# 16CH_PWM_POWER_00.net
KiCad netlist of a schematic drawn in Altium Designer
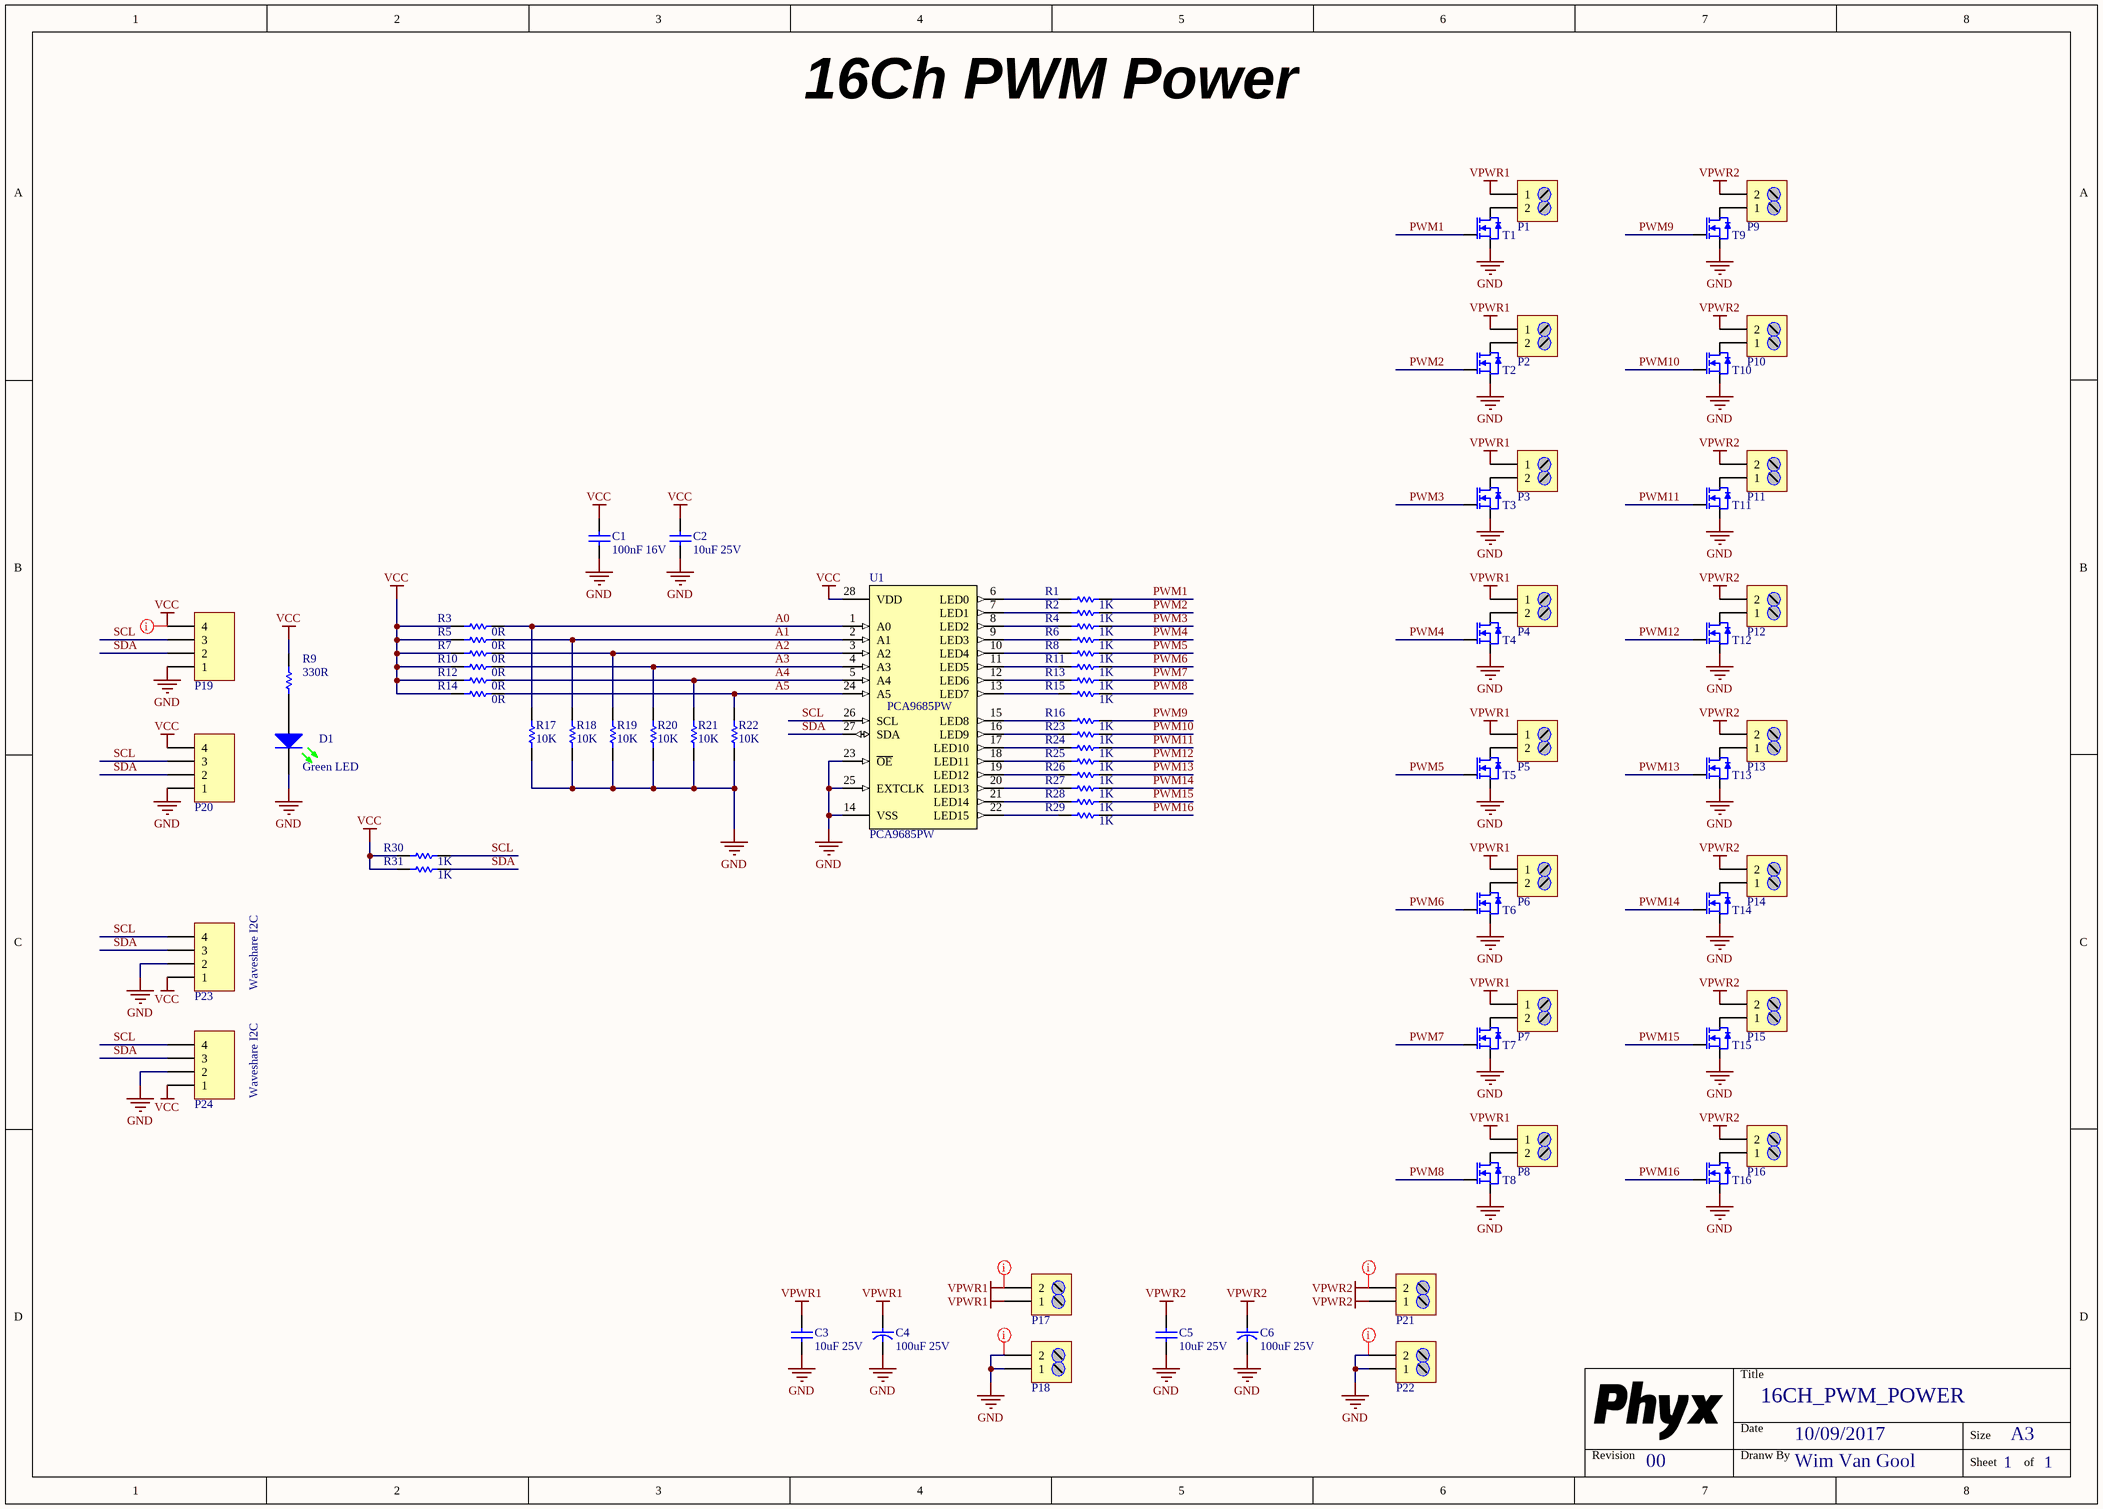
[diagram p0: 16CH_PWM_POWER_00.SchDoc]

(export (version "E")
  (design (tool "Eeschema 10.0.6"))
  (components
    (comp (ref "C1")
      (value "100nF 16V")
      (footprint "C0603_N")
      (description "Capacitor Ceramic")
      (fields (field (name "Comment") "CAP_CERAMIC"))
      (libsource (lib "Phyx_Components") (part "CAP_CERAMIC"))
    )
    (comp (ref "C2")
      (value "10uF 25V")
      (footprint "C1206_N")
      (description "Capacitor Ceramic")
      (fields (field (name "Comment") "CAP_CERAMIC"))
      (libsource (lib "Phyx_Components") (part "CAP_CERAMIC"))
    )
    (comp (ref "C3")
      (value "10uF 25V")
      (footprint "C1206_N")
      (description "Capacitor Ceramic")
      (fields (field (name "Comment") "CAP_CERAMIC"))
      (libsource (lib "Phyx_Components") (part "CAP_CERAMIC"))
    )
    (comp (ref "C4")
      (value "100uF 25V")
      (footprint "C_8x11.5_3.5mm")
      (description "Capacitor electrolyt")
      (fields (field (name "Comment") "CAP_POL"))
      (libsource (lib "Phyx_Components") (part "CAP_POL"))
    )
    (comp (ref "C5")
      (value "10uF 25V")
      (footprint "C1206_N")
      (description "Capacitor Ceramic")
      (fields (field (name "Comment") "CAP_CERAMIC"))
      (libsource (lib "Phyx_Components") (part "CAP_CERAMIC"))
    )
    (comp (ref "C6")
      (value "100uF 25V")
      (footprint "C_8x11.5_3.5mm")
      (description "Capacitor electrolyt")
      (fields (field (name "Comment") "CAP_POL"))
      (libsource (lib "Phyx_Components") (part "CAP_POL"))
    )
    (comp (ref "D1")
      (value "Green LED")
      (footprint "LED_0805_GR")
      (description "=Description")
      (libsource (lib "Phyx_Components") (part "LED_GREEN"))
    )
    (comp (ref "P1")
      (value "2 Way Screw HDR 3,5mm")
      (footprint "WE_691103110002")
      (libsource (lib "Phyx_Components") (part "TERM_BLCK_2"))
    )
    (comp (ref "P2")
      (value "2 Way Screw HDR 3,5mm")
      (footprint "WE_691103110002")
      (libsource (lib "Phyx_Components") (part "TERM_BLCK_2"))
    )
    (comp (ref "P3")
      (value "2 Way Screw HDR 3,5mm")
      (footprint "WE_691103110002")
      (libsource (lib "Phyx_Components") (part "TERM_BLCK_2"))
    )
    (comp (ref "P4")
      (value "2 Way Screw HDR 3,5mm")
      (footprint "WE_691103110002")
      (libsource (lib "Phyx_Components") (part "TERM_BLCK_2"))
    )
    (comp (ref "P5")
      (value "2 Way Screw HDR 3,5mm")
      (footprint "WE_691103110002")
      (libsource (lib "Phyx_Components") (part "TERM_BLCK_2"))
    )
    (comp (ref "P6")
      (value "2 Way Screw HDR 3,5mm")
      (footprint "WE_691103110002")
      (libsource (lib "Phyx_Components") (part "TERM_BLCK_2"))
    )
    (comp (ref "P7")
      (value "2 Way Screw HDR 3,5mm")
      (footprint "WE_691103110002")
      (libsource (lib "Phyx_Components") (part "TERM_BLCK_2"))
    )
    (comp (ref "P8")
      (value "2 Way Screw HDR 3,5mm")
      (footprint "WE_691103110002")
      (libsource (lib "Phyx_Components") (part "TERM_BLCK_2"))
    )
    (comp (ref "P9")
      (value "2 Way Screw HDR 3,5mm")
      (footprint "WE_691103110002")
      (libsource (lib "") (part "TERM_BLCK_2_1"))
    )
    (comp (ref "P10")
      (value "2 Way Screw HDR 3,5mm")
      (footprint "WE_691103110002")
      (libsource (lib "") (part "TERM_BLCK_2_1"))
    )
    (comp (ref "P11")
      (value "2 Way Screw HDR 3,5mm")
      (footprint "WE_691103110002")
      (libsource (lib "") (part "TERM_BLCK_2_1"))
    )
    (comp (ref "P12")
      (value "2 Way Screw HDR 3,5mm")
      (footprint "WE_691103110002")
      (libsource (lib "") (part "TERM_BLCK_2_1"))
    )
    (comp (ref "P13")
      (value "2 Way Screw HDR 3,5mm")
      (footprint "WE_691103110002")
      (libsource (lib "") (part "TERM_BLCK_2_1"))
    )
    (comp (ref "P14")
      (value "2 Way Screw HDR 3,5mm")
      (footprint "WE_691103110002")
      (libsource (lib "") (part "TERM_BLCK_2_1"))
    )
    (comp (ref "P15")
      (value "2 Way Screw HDR 3,5mm")
      (footprint "WE_691103110002")
      (libsource (lib "") (part "TERM_BLCK_2_1"))
    )
    (comp (ref "P16")
      (value "2 Way Screw HDR 3,5mm")
      (footprint "WE_691103110002")
      (libsource (lib "") (part "TERM_BLCK_2_1"))
    )
    (comp (ref "P17")
      (value "2 Way Screw HDR 3,5mm")
      (footprint "WE_691103110002")
      (libsource (lib "") (part "TERM_BLCK_2_1"))
    )
    (comp (ref "P18")
      (value "2 Way Screw HDR 3,5mm")
      (footprint "WE_691103110002")
      (libsource (lib "") (part "TERM_BLCK_2_1"))
    )
    (comp (ref "P19")
      (value "Header 4")
      (footprint "HDR1X4")
      (libsource (lib "Phyx_Components") (part "Header 4"))
    )
    (comp (ref "P20")
      (value "Header 4")
      (footprint "HDR1X4")
      (libsource (lib "Phyx_Components") (part "Header 4"))
    )
    (comp (ref "P21")
      (value "2 Way Screw HDR 3,5mm")
      (footprint "WE_691103110002")
      (libsource (lib "") (part "TERM_BLCK_2_1"))
    )
    (comp (ref "P22")
      (value "2 Way Screw HDR 3,5mm")
      (footprint "WE_691103110002")
      (libsource (lib "") (part "TERM_BLCK_2_1"))
    )
    (comp (ref "P23")
      (value "Header 4")
      (footprint "HDR1X4")
      (libsource (lib "Phyx_Components") (part "Header 4"))
    )
    (comp (ref "P24")
      (value "Header 4")
      (footprint "HDR1X4")
      (libsource (lib "Phyx_Components") (part "Header 4"))
    )
    (comp (ref "R1")
      (value "1K")
      (footprint "R0603_N")
      (fields (field (name "Comment") "RESISTOR"))
      (libsource (lib "Phyx_Components") (part "RESISTOR"))
    )
    (comp (ref "R2")
      (value "1K")
      (footprint "R0603_N")
      (fields (field (name "Comment") "RESISTOR"))
      (libsource (lib "Phyx_Components") (part "RESISTOR"))
    )
    (comp (ref "R3")
      (value "0R")
      (footprint "R0603_N")
      (fields (field (name "Comment") "RESISTOR"))
      (libsource (lib "Phyx_Components") (part "RESISTOR"))
    )
    (comp (ref "R4")
      (value "1K")
      (footprint "R0603_N")
      (fields (field (name "Comment") "RESISTOR"))
      (libsource (lib "Phyx_Components") (part "RESISTOR"))
    )
    (comp (ref "R5")
      (value "0R")
      (footprint "R0603_N")
      (fields (field (name "Comment") "RESISTOR"))
      (libsource (lib "Phyx_Components") (part "RESISTOR"))
    )
    (comp (ref "R6")
      (value "1K")
      (footprint "R0603_N")
      (fields (field (name "Comment") "RESISTOR"))
      (libsource (lib "Phyx_Components") (part "RESISTOR"))
    )
    (comp (ref "R7")
      (value "0R")
      (footprint "R0603_N")
      (fields (field (name "Comment") "RESISTOR"))
      (libsource (lib "Phyx_Components") (part "RESISTOR"))
    )
    (comp (ref "R8")
      (value "1K")
      (footprint "R0603_N")
      (fields (field (name "Comment") "RESISTOR"))
      (libsource (lib "Phyx_Components") (part "RESISTOR"))
    )
    (comp (ref "R9")
      (value "330R")
      (footprint "R0603_N")
      (fields (field (name "Comment") "RESISTOR"))
      (libsource (lib "Phyx_Components") (part "RESISTOR"))
    )
    (comp (ref "R10")
      (value "0R")
      (footprint "R0603_N")
      (fields (field (name "Comment") "RESISTOR"))
      (libsource (lib "Phyx_Components") (part "RESISTOR"))
    )
    (comp (ref "R11")
      (value "1K")
      (footprint "R0603_N")
      (fields (field (name "Comment") "RESISTOR"))
      (libsource (lib "Phyx_Components") (part "RESISTOR"))
    )
    (comp (ref "R12")
      (value "0R")
      (footprint "R0603_N")
      (fields (field (name "Comment") "RESISTOR"))
      (libsource (lib "Phyx_Components") (part "RESISTOR"))
    )
    (comp (ref "R13")
      (value "1K")
      (footprint "R0603_N")
      (fields (field (name "Comment") "RESISTOR"))
      (libsource (lib "Phyx_Components") (part "RESISTOR"))
    )
    (comp (ref "R14")
      (value "0R")
      (footprint "R0603_N")
      (fields (field (name "Comment") "RESISTOR"))
      (libsource (lib "Phyx_Components") (part "RESISTOR"))
    )
    (comp (ref "R15")
      (value "1K")
      (footprint "R0603_N")
      (fields (field (name "Comment") "RESISTOR"))
      (libsource (lib "Phyx_Components") (part "RESISTOR"))
    )
    (comp (ref "R16")
      (value "1K")
      (footprint "R0603_N")
      (fields (field (name "Comment") "RESISTOR"))
      (libsource (lib "Phyx_Components") (part "RESISTOR"))
    )
    (comp (ref "R17")
      (value "10K")
      (footprint "R0603_N")
      (fields (field (name "Comment") "RESISTOR"))
      (libsource (lib "Phyx_Components") (part "RESISTOR"))
    )
    (comp (ref "R18")
      (value "10K")
      (footprint "R0603_N")
      (fields (field (name "Comment") "RESISTOR"))
      (libsource (lib "Phyx_Components") (part "RESISTOR"))
    )
    (comp (ref "R19")
      (value "10K")
      (footprint "R0603_N")
      (fields (field (name "Comment") "RESISTOR"))
      (libsource (lib "Phyx_Components") (part "RESISTOR"))
    )
    (comp (ref "R20")
      (value "10K")
      (footprint "R0603_N")
      (fields (field (name "Comment") "RESISTOR"))
      (libsource (lib "Phyx_Components") (part "RESISTOR"))
    )
    (comp (ref "R21")
      (value "10K")
      (footprint "R0603_N")
      (fields (field (name "Comment") "RESISTOR"))
      (libsource (lib "Phyx_Components") (part "RESISTOR"))
    )
    (comp (ref "R22")
      (value "10K")
      (footprint "R0603_N")
      (fields (field (name "Comment") "RESISTOR"))
      (libsource (lib "Phyx_Components") (part "RESISTOR"))
    )
    (comp (ref "R23")
      (value "1K")
      (footprint "R0603_N")
      (fields (field (name "Comment") "RESISTOR"))
      (libsource (lib "Phyx_Components") (part "RESISTOR"))
    )
    (comp (ref "R24")
      (value "1K")
      (footprint "R0603_N")
      (fields (field (name "Comment") "RESISTOR"))
      (libsource (lib "Phyx_Components") (part "RESISTOR"))
    )
    (comp (ref "R25")
      (value "1K")
      (footprint "R0603_N")
      (fields (field (name "Comment") "RESISTOR"))
      (libsource (lib "Phyx_Components") (part "RESISTOR"))
    )
    (comp (ref "R26")
      (value "1K")
      (footprint "R0603_N")
      (fields (field (name "Comment") "RESISTOR"))
      (libsource (lib "Phyx_Components") (part "RESISTOR"))
    )
    (comp (ref "R27")
      (value "1K")
      (footprint "R0603_N")
      (fields (field (name "Comment") "RESISTOR"))
      (libsource (lib "Phyx_Components") (part "RESISTOR"))
    )
    (comp (ref "R28")
      (value "1K")
      (footprint "R0603_N")
      (fields (field (name "Comment") "RESISTOR"))
      (libsource (lib "Phyx_Components") (part "RESISTOR"))
    )
    (comp (ref "R29")
      (value "1K")
      (footprint "R0603_N")
      (fields (field (name "Comment") "RESISTOR"))
      (libsource (lib "Phyx_Components") (part "RESISTOR"))
    )
    (comp (ref "R30")
      (value "1K")
      (footprint "R0603_N")
      (fields (field (name "Comment") "RESISTOR"))
      (libsource (lib "Phyx_Components") (part "RESISTOR"))
    )
    (comp (ref "R31")
      (value "1K")
      (footprint "R0603_N")
      (fields (field (name "Comment") "RESISTOR"))
      (libsource (lib "Phyx_Components") (part "RESISTOR"))
    )
    (comp (ref "T1")
      (value "70A 30V N-Ch MOSFET Vgs 2.5")
      (footprint "TO-252")
      (libsource (lib "Phyx_Components") (part "N_MOSFET_GSD"))
    )
    (comp (ref "T2")
      (value "70A 30V N-Ch MOSFET Vgs 2.5")
      (footprint "TO-252")
      (libsource (lib "Phyx_Components") (part "N_MOSFET_GSD"))
    )
    (comp (ref "T3")
      (value "70A 30V N-Ch MOSFET Vgs 2.5")
      (footprint "TO-252")
      (libsource (lib "Phyx_Components") (part "N_MOSFET_GSD"))
    )
    (comp (ref "T4")
      (value "70A 30V N-Ch MOSFET Vgs 2.5")
      (footprint "TO-252")
      (libsource (lib "Phyx_Components") (part "N_MOSFET_GSD"))
    )
    (comp (ref "T5")
      (value "70A 30V N-Ch MOSFET Vgs 2.5")
      (footprint "TO-252")
      (libsource (lib "Phyx_Components") (part "N_MOSFET_GSD"))
    )
    (comp (ref "T6")
      (value "70A 30V N-Ch MOSFET Vgs 2.5")
      (footprint "TO-252")
      (libsource (lib "Phyx_Components") (part "N_MOSFET_GSD"))
    )
    (comp (ref "T7")
      (value "70A 30V N-Ch MOSFET Vgs 2.5")
      (footprint "TO-252")
      (libsource (lib "Phyx_Components") (part "N_MOSFET_GSD"))
    )
    (comp (ref "T8")
      (value "70A 30V N-Ch MOSFET Vgs 2.5")
      (footprint "TO-252")
      (libsource (lib "Phyx_Components") (part "N_MOSFET_GSD"))
    )
    (comp (ref "T9")
      (value "70A 30V N-Ch MOSFET Vgs 2.5")
      (footprint "TO-252")
      (libsource (lib "Phyx_Components") (part "N_MOSFET_GSD"))
    )
    (comp (ref "T10")
      (value "70A 30V N-Ch MOSFET Vgs 2.5")
      (footprint "TO-252")
      (libsource (lib "Phyx_Components") (part "N_MOSFET_GSD"))
    )
    (comp (ref "T11")
      (value "70A 30V N-Ch MOSFET Vgs 2.5")
      (footprint "TO-252")
      (libsource (lib "Phyx_Components") (part "N_MOSFET_GSD"))
    )
    (comp (ref "T12")
      (value "70A 30V N-Ch MOSFET Vgs 2.5")
      (footprint "TO-252")
      (libsource (lib "Phyx_Components") (part "N_MOSFET_GSD"))
    )
    (comp (ref "T13")
      (value "70A 30V N-Ch MOSFET Vgs 2.5")
      (footprint "TO-252")
      (libsource (lib "Phyx_Components") (part "N_MOSFET_GSD"))
    )
    (comp (ref "T14")
      (value "70A 30V N-Ch MOSFET Vgs 2.5")
      (footprint "TO-252")
      (libsource (lib "Phyx_Components") (part "N_MOSFET_GSD"))
    )
    (comp (ref "T15")
      (value "70A 30V N-Ch MOSFET Vgs 2.5")
      (footprint "TO-252")
      (libsource (lib "Phyx_Components") (part "N_MOSFET_GSD"))
    )
    (comp (ref "T16")
      (value "70A 30V N-Ch MOSFET Vgs 2.5")
      (footprint "TO-252")
      (libsource (lib "Phyx_Components") (part "N_MOSFET_GSD"))
    )
    (comp (ref "U1")
      (value "PCA9685PW")
      (footprint "NXP_SOT361-1")
      (description "=Description")
      (fields (field (name "Comment") "I2C 12-bit 16Ch PWM"))
      (libsource (lib "Phyx_Components") (part "PCA9685PW"))
    )
  )
  (nets
    (net (code "1") (name "/A0") (class "Default")
      (node (ref "R17") (pin "1") (pinfunction "1_1") (pintype "passive"))
      (node (ref "R3") (pin "2") (pinfunction "2_2") (pintype "passive"))
      (node (ref "U1") (pin "1") (pinfunction "A0_1") (pintype "input"))
    )
    (net (code "2") (name "/A1") (class "Default")
      (node (ref "R18") (pin "1") (pinfunction "1_1") (pintype "passive"))
      (node (ref "R5") (pin "2") (pinfunction "2_2") (pintype "passive"))
      (node (ref "U1") (pin "2") (pinfunction "A1_2") (pintype "input"))
    )
    (net (code "3") (name "/A2") (class "Default")
      (node (ref "R19") (pin "1") (pinfunction "1_1") (pintype "passive"))
      (node (ref "R7") (pin "2") (pinfunction "2_2") (pintype "passive"))
      (node (ref "U1") (pin "3") (pinfunction "A2_3") (pintype "input"))
    )
    (net (code "4") (name "/A3") (class "Default")
      (node (ref "R10") (pin "2") (pinfunction "2_2") (pintype "passive"))
      (node (ref "R20") (pin "1") (pinfunction "1_1") (pintype "passive"))
      (node (ref "U1") (pin "4") (pinfunction "A3_4") (pintype "input"))
    )
    (net (code "5") (name "/A4") (class "Default")
      (node (ref "R12") (pin "2") (pinfunction "2_2") (pintype "passive"))
      (node (ref "R21") (pin "1") (pinfunction "1_1") (pintype "passive"))
      (node (ref "U1") (pin "5") (pinfunction "A4_5") (pintype "input"))
    )
    (net (code "6") (name "/A5") (class "Default")
      (node (ref "R14") (pin "2") (pinfunction "2_2") (pintype "passive"))
      (node (ref "R22") (pin "1") (pinfunction "1_1") (pintype "passive"))
      (node (ref "U1") (pin "24") (pinfunction "A5_24") (pintype "input"))
    )
    (net (code "7") (name "/PWM1") (class "Default")
      (node (ref "R1") (pin "1") (pinfunction "1_1") (pintype "passive"))
      (node (ref "T1") (pin "1") (pinfunction "G_1") (pintype "passive"))
    )
    (net (code "8") (name "/PWM2") (class "Default")
      (node (ref "R2") (pin "1") (pinfunction "1_1") (pintype "passive"))
      (node (ref "T2") (pin "1") (pinfunction "G_1") (pintype "passive"))
    )
    (net (code "9") (name "/PWM3") (class "Default")
      (node (ref "R4") (pin "1") (pinfunction "1_1") (pintype "passive"))
      (node (ref "T3") (pin "1") (pinfunction "G_1") (pintype "passive"))
    )
    (net (code "10") (name "/PWM4") (class "Default")
      (node (ref "R6") (pin "1") (pinfunction "1_1") (pintype "passive"))
      (node (ref "T4") (pin "1") (pinfunction "G_1") (pintype "passive"))
    )
    (net (code "11") (name "/PWM5") (class "Default")
      (node (ref "R8") (pin "1") (pinfunction "1_1") (pintype "passive"))
      (node (ref "T5") (pin "1") (pinfunction "G_1") (pintype "passive"))
    )
    (net (code "12") (name "/PWM6") (class "Default")
      (node (ref "R11") (pin "1") (pinfunction "1_1") (pintype "passive"))
      (node (ref "T6") (pin "1") (pinfunction "G_1") (pintype "passive"))
    )
    (net (code "13") (name "/PWM7") (class "Default")
      (node (ref "R13") (pin "1") (pinfunction "1_1") (pintype "passive"))
      (node (ref "T7") (pin "1") (pinfunction "G_1") (pintype "passive"))
    )
    (net (code "14") (name "/PWM8") (class "Default")
      (node (ref "R15") (pin "1") (pinfunction "1_1") (pintype "passive"))
      (node (ref "T8") (pin "1") (pinfunction "G_1") (pintype "passive"))
    )
    (net (code "15") (name "/PWM9") (class "Default")
      (node (ref "R16") (pin "1") (pinfunction "1_1") (pintype "passive"))
      (node (ref "T9") (pin "1") (pinfunction "G_1") (pintype "passive"))
    )
    (net (code "16") (name "/PWM10") (class "Default")
      (node (ref "R23") (pin "1") (pinfunction "1_1") (pintype "passive"))
      (node (ref "T10") (pin "1") (pinfunction "G_1") (pintype "passive"))
    )
    (net (code "17") (name "/PWM11") (class "Default")
      (node (ref "R24") (pin "1") (pinfunction "1_1") (pintype "passive"))
      (node (ref "T11") (pin "1") (pinfunction "G_1") (pintype "passive"))
    )
    (net (code "18") (name "/PWM12") (class "Default")
      (node (ref "R25") (pin "1") (pinfunction "1_1") (pintype "passive"))
      (node (ref "T12") (pin "1") (pinfunction "G_1") (pintype "passive"))
    )
    (net (code "19") (name "/PWM13") (class "Default")
      (node (ref "R26") (pin "1") (pinfunction "1_1") (pintype "passive"))
      (node (ref "T13") (pin "1") (pinfunction "G_1") (pintype "passive"))
    )
    (net (code "20") (name "/PWM14") (class "Default")
      (node (ref "R27") (pin "1") (pinfunction "1_1") (pintype "passive"))
      (node (ref "T14") (pin "1") (pinfunction "G_1") (pintype "passive"))
    )
    (net (code "21") (name "/PWM15") (class "Default")
      (node (ref "R28") (pin "1") (pinfunction "1_1") (pintype "passive"))
      (node (ref "T15") (pin "1") (pinfunction "G_1") (pintype "passive"))
    )
    (net (code "22") (name "/PWM16") (class "Default")
      (node (ref "R29") (pin "1") (pinfunction "1_1") (pintype "passive"))
      (node (ref "T16") (pin "1") (pinfunction "G_1") (pintype "passive"))
    )
    (net (code "23") (name "/SCL") (class "Default")
      (node (ref "P19") (pin "3") (pinfunction "3_3") (pintype "passive"))
      (node (ref "P20") (pin "3") (pinfunction "3_3") (pintype "passive"))
      (node (ref "P23") (pin "4") (pinfunction "4_4") (pintype "passive"))
      (node (ref "P24") (pin "4") (pinfunction "4_4") (pintype "passive"))
      (node (ref "R30") (pin "1") (pinfunction "1_1") (pintype "passive"))
      (node (ref "U1") (pin "26") (pinfunction "SCL_26") (pintype "input"))
    )
    (net (code "24") (name "/SDA") (class "Default")
      (node (ref "P19") (pin "2") (pinfunction "2_2") (pintype "passive"))
      (node (ref "P20") (pin "2") (pinfunction "2_2") (pintype "passive"))
      (node (ref "P23") (pin "3") (pinfunction "3_3") (pintype "passive"))
      (node (ref "P24") (pin "3") (pinfunction "3_3") (pintype "passive"))
      (node (ref "R31") (pin "1") (pinfunction "1_1") (pintype "passive"))
      (node (ref "U1") (pin "27") (pinfunction "SDA_27") (pintype "bidirectional"))
    )
    (net (code "25") (name "GND") (class "Default")
      (node (ref "C1") (pin "2") (pinfunction "2_2") (pintype "passive"))
      (node (ref "C2") (pin "2") (pinfunction "2_2") (pintype "passive"))
      (node (ref "C3") (pin "2") (pinfunction "2_2") (pintype "passive"))
      (node (ref "C4") (pin "2") (pinfunction "2_2") (pintype "passive"))
      (node (ref "C5") (pin "2") (pinfunction "2_2") (pintype "passive"))
      (node (ref "C6") (pin "2") (pinfunction "2_2") (pintype "passive"))
      (node (ref "D1") (pin "2") (pinfunction "K_2") (pintype "passive"))
      (node (ref "P18") (pin "1") (pinfunction "1_1") (pintype "passive"))
      (node (ref "P18") (pin "2") (pinfunction "2_2") (pintype "passive"))
      (node (ref "P19") (pin "1") (pinfunction "1_1") (pintype "passive"))
      (node (ref "P20") (pin "1") (pinfunction "1_1") (pintype "passive"))
      (node (ref "P22") (pin "1") (pinfunction "1_1") (pintype "passive"))
      (node (ref "P22") (pin "2") (pinfunction "2_2") (pintype "passive"))
      (node (ref "P23") (pin "2") (pinfunction "2_2") (pintype "passive"))
      (node (ref "P24") (pin "2") (pinfunction "2_2") (pintype "passive"))
      (node (ref "R17") (pin "2") (pinfunction "2_2") (pintype "passive"))
      (node (ref "R18") (pin "2") (pinfunction "2_2") (pintype "passive"))
      (node (ref "R19") (pin "2") (pinfunction "2_2") (pintype "passive"))
      (node (ref "R20") (pin "2") (pinfunction "2_2") (pintype "passive"))
      (node (ref "R21") (pin "2") (pinfunction "2_2") (pintype "passive"))
      (node (ref "R22") (pin "2") (pinfunction "2_2") (pintype "passive"))
      (node (ref "T1") (pin "2") (pinfunction "S_2") (pintype "passive"))
      (node (ref "T10") (pin "2") (pinfunction "S_2") (pintype "passive"))
      (node (ref "T11") (pin "2") (pinfunction "S_2") (pintype "passive"))
      (node (ref "T12") (pin "2") (pinfunction "S_2") (pintype "passive"))
      (node (ref "T13") (pin "2") (pinfunction "S_2") (pintype "passive"))
      (node (ref "T14") (pin "2") (pinfunction "S_2") (pintype "passive"))
      (node (ref "T15") (pin "2") (pinfunction "S_2") (pintype "passive"))
      (node (ref "T16") (pin "2") (pinfunction "S_2") (pintype "passive"))
      (node (ref "T2") (pin "2") (pinfunction "S_2") (pintype "passive"))
      (node (ref "T3") (pin "2") (pinfunction "S_2") (pintype "passive"))
      (node (ref "T4") (pin "2") (pinfunction "S_2") (pintype "passive"))
      (node (ref "T5") (pin "2") (pinfunction "S_2") (pintype "passive"))
      (node (ref "T6") (pin "2") (pinfunction "S_2") (pintype "passive"))
      (node (ref "T7") (pin "2") (pinfunction "S_2") (pintype "passive"))
      (node (ref "T8") (pin "2") (pinfunction "S_2") (pintype "passive"))
      (node (ref "T9") (pin "2") (pinfunction "S_2") (pintype "passive"))
      (node (ref "U1") (pin "14") (pinfunction "VSS_14") (pintype "power_in"))
      (node (ref "U1") (pin "23") (pinfunction "~{OE}_23") (pintype "input"))
      (node (ref "U1") (pin "25") (pinfunction "EXTCLK_25") (pintype "input"))
    )
    (net (code "26") (name "Net-(D1-A)") (class "Default")
      (node (ref "D1") (pin "1") (pinfunction "A_1") (pintype "passive"))
      (node (ref "R9") (pin "2") (pinfunction "2_2") (pintype "passive"))
    )
    (net (code "27") (name "Net-(T1-D)") (class "Default")
      (node (ref "P1") (pin "2") (pinfunction "2_2") (pintype "passive"))
      (node (ref "T1") (pin "3") (pinfunction "D_3") (pintype "passive"))
    )
    (net (code "28") (name "Net-(T2-D)") (class "Default")
      (node (ref "P2") (pin "2") (pinfunction "2_2") (pintype "passive"))
      (node (ref "T2") (pin "3") (pinfunction "D_3") (pintype "passive"))
    )
    (net (code "29") (name "Net-(T3-D)") (class "Default")
      (node (ref "P3") (pin "2") (pinfunction "2_2") (pintype "passive"))
      (node (ref "T3") (pin "3") (pinfunction "D_3") (pintype "passive"))
    )
    (net (code "30") (name "Net-(T4-D)") (class "Default")
      (node (ref "P4") (pin "2") (pinfunction "2_2") (pintype "passive"))
      (node (ref "T4") (pin "3") (pinfunction "D_3") (pintype "passive"))
    )
    (net (code "31") (name "Net-(T5-D)") (class "Default")
      (node (ref "P5") (pin "2") (pinfunction "2_2") (pintype "passive"))
      (node (ref "T5") (pin "3") (pinfunction "D_3") (pintype "passive"))
    )
    (net (code "32") (name "Net-(T6-D)") (class "Default")
      (node (ref "P6") (pin "2") (pinfunction "2_2") (pintype "passive"))
      (node (ref "T6") (pin "3") (pinfunction "D_3") (pintype "passive"))
    )
    (net (code "33") (name "Net-(T7-D)") (class "Default")
      (node (ref "P7") (pin "2") (pinfunction "2_2") (pintype "passive"))
      (node (ref "T7") (pin "3") (pinfunction "D_3") (pintype "passive"))
    )
    (net (code "34") (name "Net-(T8-D)") (class "Default")
      (node (ref "P8") (pin "2") (pinfunction "2_2") (pintype "passive"))
      (node (ref "T8") (pin "3") (pinfunction "D_3") (pintype "passive"))
    )
    (net (code "35") (name "Net-(T9-D)") (class "Default")
      (node (ref "P9") (pin "1") (pinfunction "1_1") (pintype "passive"))
      (node (ref "T9") (pin "3") (pinfunction "D_3") (pintype "passive"))
    )
    (net (code "36") (name "Net-(T10-D)") (class "Default")
      (node (ref "P10") (pin "1") (pinfunction "1_1") (pintype "passive"))
      (node (ref "T10") (pin "3") (pinfunction "D_3") (pintype "passive"))
    )
    (net (code "37") (name "Net-(T11-D)") (class "Default")
      (node (ref "P11") (pin "1") (pinfunction "1_1") (pintype "passive"))
      (node (ref "T11") (pin "3") (pinfunction "D_3") (pintype "passive"))
    )
    (net (code "38") (name "Net-(T12-D)") (class "Default")
      (node (ref "P12") (pin "1") (pinfunction "1_1") (pintype "passive"))
      (node (ref "T12") (pin "3") (pinfunction "D_3") (pintype "passive"))
    )
    (net (code "39") (name "Net-(T13-D)") (class "Default")
      (node (ref "P13") (pin "1") (pinfunction "1_1") (pintype "passive"))
      (node (ref "T13") (pin "3") (pinfunction "D_3") (pintype "passive"))
    )
    (net (code "40") (name "Net-(T14-D)") (class "Default")
      (node (ref "P14") (pin "1") (pinfunction "1_1") (pintype "passive"))
      (node (ref "T14") (pin "3") (pinfunction "D_3") (pintype "passive"))
    )
    (net (code "41") (name "Net-(T15-D)") (class "Default")
      (node (ref "P15") (pin "1") (pinfunction "1_1") (pintype "passive"))
      (node (ref "T15") (pin "3") (pinfunction "D_3") (pintype "passive"))
    )
    (net (code "42") (name "Net-(T16-D)") (class "Default")
      (node (ref "P16") (pin "1") (pinfunction "1_1") (pintype "passive"))
      (node (ref "T16") (pin "3") (pinfunction "D_3") (pintype "passive"))
    )
    (net (code "43") (name "Net-(U1-LED0)") (class "Default")
      (node (ref "R1") (pin "2") (pinfunction "2_2") (pintype "passive"))
      (node (ref "U1") (pin "6") (pinfunction "LED0_6") (pintype "output"))
    )
    (net (code "44") (name "Net-(U1-LED1)") (class "Default")
      (node (ref "R2") (pin "2") (pinfunction "2_2") (pintype "passive"))
      (node (ref "U1") (pin "7") (pinfunction "LED1_7") (pintype "output"))
    )
    (net (code "45") (name "Net-(U1-LED2)") (class "Default")
      (node (ref "R4") (pin "2") (pinfunction "2_2") (pintype "passive"))
      (node (ref "U1") (pin "8") (pinfunction "LED2_8") (pintype "output"))
    )
    (net (code "46") (name "Net-(U1-LED3)") (class "Default")
      (node (ref "R6") (pin "2") (pinfunction "2_2") (pintype "passive"))
      (node (ref "U1") (pin "9") (pinfunction "LED3_9") (pintype "output"))
    )
    (net (code "47") (name "Net-(U1-LED4)") (class "Default")
      (node (ref "R8") (pin "2") (pinfunction "2_2") (pintype "passive"))
      (node (ref "U1") (pin "10") (pinfunction "LED4_10") (pintype "output"))
    )
    (net (code "48") (name "Net-(U1-LED5)") (class "Default")
      (node (ref "R11") (pin "2") (pinfunction "2_2") (pintype "passive"))
      (node (ref "U1") (pin "11") (pinfunction "LED5_11") (pintype "output"))
    )
    (net (code "49") (name "Net-(U1-LED6)") (class "Default")
      (node (ref "R13") (pin "2") (pinfunction "2_2") (pintype "passive"))
      (node (ref "U1") (pin "12") (pinfunction "LED6_12") (pintype "output"))
    )
    (net (code "50") (name "Net-(U1-LED7)") (class "Default")
      (node (ref "R15") (pin "2") (pinfunction "2_2") (pintype "passive"))
      (node (ref "U1") (pin "13") (pinfunction "LED7_13") (pintype "output"))
    )
    (net (code "51") (name "Net-(U1-LED8)") (class "Default")
      (node (ref "R16") (pin "2") (pinfunction "2_2") (pintype "passive"))
      (node (ref "U1") (pin "15") (pinfunction "LED8_15") (pintype "output"))
    )
    (net (code "52") (name "Net-(U1-LED9)") (class "Default")
      (node (ref "R23") (pin "2") (pinfunction "2_2") (pintype "passive"))
      (node (ref "U1") (pin "16") (pinfunction "LED9_16") (pintype "output"))
    )
    (net (code "53") (name "Net-(U1-LED10)") (class "Default")
      (node (ref "R24") (pin "2") (pinfunction "2_2") (pintype "passive"))
      (node (ref "U1") (pin "17") (pinfunction "LED10_17") (pintype "output"))
    )
    (net (code "54") (name "Net-(U1-LED11)") (class "Default")
      (node (ref "R25") (pin "2") (pinfunction "2_2") (pintype "passive"))
      (node (ref "U1") (pin "18") (pinfunction "LED11_18") (pintype "output"))
    )
    (net (code "55") (name "Net-(U1-LED12)") (class "Default")
      (node (ref "R26") (pin "2") (pinfunction "2_2") (pintype "passive"))
      (node (ref "U1") (pin "19") (pinfunction "LED12_19") (pintype "output"))
    )
    (net (code "56") (name "Net-(U1-LED13)") (class "Default")
      (node (ref "R27") (pin "2") (pinfunction "2_2") (pintype "passive"))
      (node (ref "U1") (pin "20") (pinfunction "LED13_20") (pintype "output"))
    )
    (net (code "57") (name "Net-(U1-LED14)") (class "Default")
      (node (ref "R28") (pin "2") (pinfunction "2_2") (pintype "passive"))
      (node (ref "U1") (pin "21") (pinfunction "LED14_21") (pintype "output"))
    )
    (net (code "58") (name "Net-(U1-LED15)") (class "Default")
      (node (ref "R29") (pin "2") (pinfunction "2_2") (pintype "passive"))
      (node (ref "U1") (pin "22") (pinfunction "LED15_22") (pintype "output"))
    )
    (net (code "59") (name "VCC") (class "Default")
      (node (ref "C1") (pin "1") (pinfunction "1_1") (pintype "passive"))
      (node (ref "C2") (pin "1") (pinfunction "1_1") (pintype "passive"))
      (node (ref "P19") (pin "4") (pinfunction "4_4") (pintype "passive"))
      (node (ref "P20") (pin "4") (pinfunction "4_4") (pintype "passive"))
      (node (ref "P23") (pin "1") (pinfunction "1_1") (pintype "passive"))
      (node (ref "P24") (pin "1") (pinfunction "1_1") (pintype "passive"))
      (node (ref "R10") (pin "1") (pinfunction "1_1") (pintype "passive"))
      (node (ref "R12") (pin "1") (pinfunction "1_1") (pintype "passive"))
      (node (ref "R14") (pin "1") (pinfunction "1_1") (pintype "passive"))
      (node (ref "R3") (pin "1") (pinfunction "1_1") (pintype "passive"))
      (node (ref "R30") (pin "2") (pinfunction "2_2") (pintype "passive"))
      (node (ref "R31") (pin "2") (pinfunction "2_2") (pintype "passive"))
      (node (ref "R5") (pin "1") (pinfunction "1_1") (pintype "passive"))
      (node (ref "R7") (pin "1") (pinfunction "1_1") (pintype "passive"))
      (node (ref "R9") (pin "1") (pinfunction "1_1") (pintype "passive"))
      (node (ref "U1") (pin "28") (pinfunction "VDD_28") (pintype "power_in"))
    )
    (net (code "60") (name "VPWR1") (class "Default")
      (node (ref "C3") (pin "1") (pinfunction "1_1") (pintype "passive"))
      (node (ref "C4") (pin "1") (pinfunction "1_1") (pintype "passive"))
      (node (ref "P1") (pin "1") (pinfunction "1_1") (pintype "passive"))
      (node (ref "P17") (pin "1") (pinfunction "1_1") (pintype "passive"))
      (node (ref "P17") (pin "2") (pinfunction "2_2") (pintype "passive"))
      (node (ref "P2") (pin "1") (pinfunction "1_1") (pintype "passive"))
      (node (ref "P3") (pin "1") (pinfunction "1_1") (pintype "passive"))
      (node (ref "P4") (pin "1") (pinfunction "1_1") (pintype "passive"))
      (node (ref "P5") (pin "1") (pinfunction "1_1") (pintype "passive"))
      (node (ref "P6") (pin "1") (pinfunction "1_1") (pintype "passive"))
      (node (ref "P7") (pin "1") (pinfunction "1_1") (pintype "passive"))
      (node (ref "P8") (pin "1") (pinfunction "1_1") (pintype "passive"))
    )
    (net (code "61") (name "VPWR2") (class "Default")
      (node (ref "C5") (pin "1") (pinfunction "1_1") (pintype "passive"))
      (node (ref "C6") (pin "1") (pinfunction "1_1") (pintype "passive"))
      (node (ref "P10") (pin "2") (pinfunction "2_2") (pintype "passive"))
      (node (ref "P11") (pin "2") (pinfunction "2_2") (pintype "passive"))
      (node (ref "P12") (pin "2") (pinfunction "2_2") (pintype "passive"))
      (node (ref "P13") (pin "2") (pinfunction "2_2") (pintype "passive"))
      (node (ref "P14") (pin "2") (pinfunction "2_2") (pintype "passive"))
      (node (ref "P15") (pin "2") (pinfunction "2_2") (pintype "passive"))
      (node (ref "P16") (pin "2") (pinfunction "2_2") (pintype "passive"))
      (node (ref "P21") (pin "1") (pinfunction "1_1") (pintype "passive"))
      (node (ref "P21") (pin "2") (pinfunction "2_2") (pintype "passive"))
      (node (ref "P9") (pin "2") (pinfunction "2_2") (pintype "passive"))
    )
  )
)
